# V72_A33.net
KiCad netlist of a schematic drawn in Altium Designer
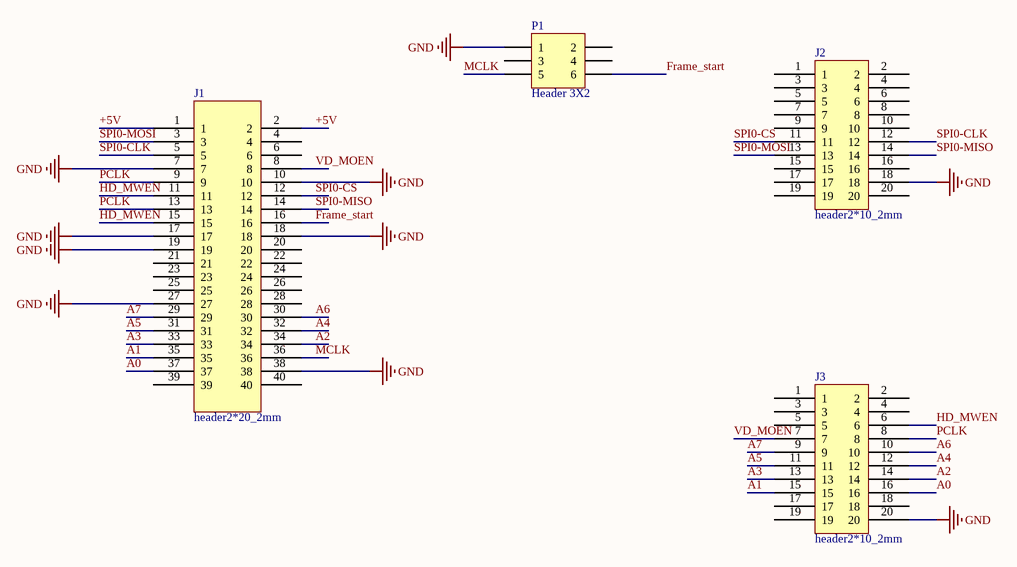
[diagram p0: V72_A33.SchDoc]

(export (version "E")
  (design (tool "Eeschema 10.0.6"))
  (components
    (comp (ref "J1")
      (value "header2*20_2mm")
      (footprint "header2*20_2mm")
      (libsource (lib "Schlib1") (part "header2*20_2mm"))
    )
    (comp (ref "J2")
      (value "header2*10_2mm")
      (footprint "header2*10_2mm")
      (libsource (lib "Schlib1") (part "header2*10_2mm"))
    )
    (comp (ref "J3")
      (value "header2*10_2mm")
      (footprint "header2*10_2mm")
      (libsource (lib "Schlib1") (part "header2*10_2mm"))
    )
    (comp (ref "P1")
      (value "Header 3X2")
      (footprint "HDR2X3")
      (description "Header, 3-Pin, Dual row")
      (fields (field (name "PUBLISHER") "Altium Limited"))
      (libsource (lib "Miscellaneous Connectors") (part "Header 3X2"))
    )
  )
  (nets
    (net (code "1") (name "/+5V") (class "Default")
      (node (ref "J1") (pin "1") (pinfunction "1_1") (pintype "passive"))
      (node (ref "J1") (pin "2") (pinfunction "2_2") (pintype "passive"))
    )
    (net (code "2") (name "/A0") (class "Default")
      (node (ref "J1") (pin "37") (pinfunction "37_37") (pintype "passive"))
      (node (ref "J3") (pin "16") (pinfunction "16_16") (pintype "passive"))
    )
    (net (code "3") (name "/A1") (class "Default")
      (node (ref "J1") (pin "35") (pinfunction "35_35") (pintype "passive"))
      (node (ref "J3") (pin "15") (pinfunction "15_15") (pintype "passive"))
    )
    (net (code "4") (name "/A2") (class "Default")
      (node (ref "J1") (pin "34") (pinfunction "34_34") (pintype "passive"))
      (node (ref "J3") (pin "14") (pinfunction "14_14") (pintype "passive"))
    )
    (net (code "5") (name "/A3") (class "Default")
      (node (ref "J1") (pin "33") (pinfunction "33_33") (pintype "passive"))
      (node (ref "J3") (pin "13") (pinfunction "13_13") (pintype "passive"))
    )
    (net (code "6") (name "/A4") (class "Default")
      (node (ref "J1") (pin "32") (pinfunction "32_32") (pintype "passive"))
      (node (ref "J3") (pin "12") (pinfunction "12_12") (pintype "passive"))
    )
    (net (code "7") (name "/A5") (class "Default")
      (node (ref "J1") (pin "31") (pinfunction "31_31") (pintype "passive"))
      (node (ref "J3") (pin "11") (pinfunction "11_11") (pintype "passive"))
    )
    (net (code "8") (name "/A6") (class "Default")
      (node (ref "J1") (pin "30") (pinfunction "30_30") (pintype "passive"))
      (node (ref "J3") (pin "10") (pinfunction "10_10") (pintype "passive"))
    )
    (net (code "9") (name "/A7") (class "Default")
      (node (ref "J1") (pin "29") (pinfunction "29_29") (pintype "passive"))
      (node (ref "J3") (pin "9") (pinfunction "9_9") (pintype "passive"))
    )
    (net (code "10") (name "/Frame_start") (class "Default")
      (node (ref "J1") (pin "16") (pinfunction "16_16") (pintype "passive"))
      (node (ref "P1") (pin "6") (pinfunction "6_6") (pintype "passive"))
    )
    (net (code "11") (name "/HD_MWEN") (class "Default")
      (node (ref "J1") (pin "11") (pinfunction "11_11") (pintype "passive"))
      (node (ref "J1") (pin "15") (pinfunction "15_15") (pintype "passive"))
      (node (ref "J3") (pin "6") (pinfunction "6_6") (pintype "passive"))
    )
    (net (code "12") (name "/MCLK") (class "Default")
      (node (ref "J1") (pin "36") (pinfunction "36_36") (pintype "passive"))
      (node (ref "P1") (pin "5") (pinfunction "5_5") (pintype "passive"))
    )
    (net (code "13") (name "/PCLK") (class "Default")
      (node (ref "J1") (pin "13") (pinfunction "13_13") (pintype "passive"))
      (node (ref "J1") (pin "9") (pinfunction "9_9") (pintype "passive"))
      (node (ref "J3") (pin "8") (pinfunction "8_8") (pintype "passive"))
    )
    (net (code "14") (name "/SPI0-CLK") (class "Default")
      (node (ref "J1") (pin "5") (pinfunction "5_5") (pintype "passive"))
      (node (ref "J2") (pin "12") (pinfunction "12_12") (pintype "passive"))
    )
    (net (code "15") (name "/SPI0-CS") (class "Default")
      (node (ref "J1") (pin "12") (pinfunction "12_12") (pintype "passive"))
      (node (ref "J2") (pin "11") (pinfunction "11_11") (pintype "passive"))
    )
    (net (code "16") (name "/SPI0-MISO") (class "Default")
      (node (ref "J1") (pin "14") (pinfunction "14_14") (pintype "passive"))
      (node (ref "J2") (pin "14") (pinfunction "14_14") (pintype "passive"))
    )
    (net (code "17") (name "/SPI0-MOSI") (class "Default")
      (node (ref "J1") (pin "3") (pinfunction "3_3") (pintype "passive"))
      (node (ref "J2") (pin "13") (pinfunction "13_13") (pintype "passive"))
    )
    (net (code "18") (name "/VD_MOEN") (class "Default")
      (node (ref "J1") (pin "8") (pinfunction "8_8") (pintype "passive"))
      (node (ref "J3") (pin "7") (pinfunction "7_7") (pintype "passive"))
    )
    (net (code "19") (name "GND") (class "Default")
      (node (ref "J1") (pin "10") (pinfunction "10_10") (pintype "passive"))
      (node (ref "J1") (pin "17") (pinfunction "17_17") (pintype "passive"))
      (node (ref "J1") (pin "18") (pinfunction "18_18") (pintype "passive"))
      (node (ref "J1") (pin "19") (pinfunction "19_19") (pintype "passive"))
      (node (ref "J1") (pin "27") (pinfunction "27_27") (pintype "passive"))
      (node (ref "J1") (pin "38") (pinfunction "38_38") (pintype "passive"))
      (node (ref "J1") (pin "7") (pinfunction "7_7") (pintype "passive"))
      (node (ref "J2") (pin "18") (pinfunction "18_18") (pintype "passive"))
      (node (ref "J3") (pin "20") (pinfunction "20_20") (pintype "passive"))
      (node (ref "P1") (pin "1") (pinfunction "1_1") (pintype "passive"))
    )
    (net (code "20") (name "unconnected-(J1-Pad4)") (class "Default")
      (node (ref "J1") (pin "4") (pinfunction "4_4") (pintype "passive"))
    )
    (net (code "21") (name "unconnected-(J1-Pad6)") (class "Default")
      (node (ref "J1") (pin "6") (pinfunction "6_6") (pintype "passive"))
    )
    (net (code "22") (name "unconnected-(J1-Pad20)") (class "Default")
      (node (ref "J1") (pin "20") (pinfunction "20_20") (pintype "passive"))
    )
    (net (code "23") (name "unconnected-(J1-Pad21)") (class "Default")
      (node (ref "J1") (pin "21") (pinfunction "21_21") (pintype "passive"))
    )
    (net (code "24") (name "unconnected-(J1-Pad22)") (class "Default")
      (node (ref "J1") (pin "22") (pinfunction "22_22") (pintype "passive"))
    )
    (net (code "25") (name "unconnected-(J1-Pad23)") (class "Default")
      (node (ref "J1") (pin "23") (pinfunction "23_23") (pintype "passive"))
    )
    (net (code "26") (name "unconnected-(J1-Pad24)") (class "Default")
      (node (ref "J1") (pin "24") (pinfunction "24_24") (pintype "passive"))
    )
    (net (code "27") (name "unconnected-(J1-Pad25)") (class "Default")
      (node (ref "J1") (pin "25") (pinfunction "25_25") (pintype "passive"))
    )
    (net (code "28") (name "unconnected-(J1-Pad26)") (class "Default")
      (node (ref "J1") (pin "26") (pinfunction "26_26") (pintype "passive"))
    )
    (net (code "29") (name "unconnected-(J1-Pad28)") (class "Default")
      (node (ref "J1") (pin "28") (pinfunction "28_28") (pintype "passive"))
    )
    (net (code "30") (name "unconnected-(J1-Pad39)") (class "Default")
      (node (ref "J1") (pin "39") (pinfunction "39_39") (pintype "passive"))
    )
    (net (code "31") (name "unconnected-(J1-Pad40)") (class "Default")
      (node (ref "J1") (pin "40") (pinfunction "40_40") (pintype "passive"))
    )
    (net (code "32") (name "unconnected-(J2-Pad1)") (class "Default")
      (node (ref "J2") (pin "1") (pinfunction "1_1") (pintype "passive"))
    )
    (net (code "33") (name "unconnected-(J2-Pad2)") (class "Default")
      (node (ref "J2") (pin "2") (pinfunction "2_2") (pintype "passive"))
    )
    (net (code "34") (name "unconnected-(J2-Pad3)") (class "Default")
      (node (ref "J2") (pin "3") (pinfunction "3_3") (pintype "passive"))
    )
    (net (code "35") (name "unconnected-(J2-Pad4)") (class "Default")
      (node (ref "J2") (pin "4") (pinfunction "4_4") (pintype "passive"))
    )
    (net (code "36") (name "unconnected-(J2-Pad5)") (class "Default")
      (node (ref "J2") (pin "5") (pinfunction "5_5") (pintype "passive"))
    )
    (net (code "37") (name "unconnected-(J2-Pad6)") (class "Default")
      (node (ref "J2") (pin "6") (pinfunction "6_6") (pintype "passive"))
    )
    (net (code "38") (name "unconnected-(J2-Pad7)") (class "Default")
      (node (ref "J2") (pin "7") (pinfunction "7_7") (pintype "passive"))
    )
    (net (code "39") (name "unconnected-(J2-Pad8)") (class "Default")
      (node (ref "J2") (pin "8") (pinfunction "8_8") (pintype "passive"))
    )
    (net (code "40") (name "unconnected-(J2-Pad9)") (class "Default")
      (node (ref "J2") (pin "9") (pinfunction "9_9") (pintype "passive"))
    )
    (net (code "41") (name "unconnected-(J2-Pad10)") (class "Default")
      (node (ref "J2") (pin "10") (pinfunction "10_10") (pintype "passive"))
    )
    (net (code "42") (name "unconnected-(J2-Pad15)") (class "Default")
      (node (ref "J2") (pin "15") (pinfunction "15_15") (pintype "passive"))
    )
    (net (code "43") (name "unconnected-(J2-Pad16)") (class "Default")
      (node (ref "J2") (pin "16") (pinfunction "16_16") (pintype "passive"))
    )
    (net (code "44") (name "unconnected-(J2-Pad17)") (class "Default")
      (node (ref "J2") (pin "17") (pinfunction "17_17") (pintype "passive"))
    )
    (net (code "45") (name "unconnected-(J2-Pad19)") (class "Default")
      (node (ref "J2") (pin "19") (pinfunction "19_19") (pintype "passive"))
    )
    (net (code "46") (name "unconnected-(J2-Pad20)") (class "Default")
      (node (ref "J2") (pin "20") (pinfunction "20_20") (pintype "passive"))
    )
    (net (code "47") (name "unconnected-(J3-Pad1)") (class "Default")
      (node (ref "J3") (pin "1") (pinfunction "1_1") (pintype "passive"))
    )
    (net (code "48") (name "unconnected-(J3-Pad2)") (class "Default")
      (node (ref "J3") (pin "2") (pinfunction "2_2") (pintype "passive"))
    )
    (net (code "49") (name "unconnected-(J3-Pad3)") (class "Default")
      (node (ref "J3") (pin "3") (pinfunction "3_3") (pintype "passive"))
    )
    (net (code "50") (name "unconnected-(J3-Pad4)") (class "Default")
      (node (ref "J3") (pin "4") (pinfunction "4_4") (pintype "passive"))
    )
    (net (code "51") (name "unconnected-(J3-Pad5)") (class "Default")
      (node (ref "J3") (pin "5") (pinfunction "5_5") (pintype "passive"))
    )
    (net (code "52") (name "unconnected-(J3-Pad17)") (class "Default")
      (node (ref "J3") (pin "17") (pinfunction "17_17") (pintype "passive"))
    )
    (net (code "53") (name "unconnected-(J3-Pad18)") (class "Default")
      (node (ref "J3") (pin "18") (pinfunction "18_18") (pintype "passive"))
    )
    (net (code "54") (name "unconnected-(J3-Pad19)") (class "Default")
      (node (ref "J3") (pin "19") (pinfunction "19_19") (pintype "passive"))
    )
    (net (code "55") (name "unconnected-(P1-Pad2)") (class "Default")
      (node (ref "P1") (pin "2") (pinfunction "2_2") (pintype "passive"))
    )
    (net (code "56") (name "unconnected-(P1-Pad3)") (class "Default")
      (node (ref "P1") (pin "3") (pinfunction "3_3") (pintype "passive"))
    )
    (net (code "57") (name "unconnected-(P1-Pad4)") (class "Default")
      (node (ref "P1") (pin "4") (pinfunction "4_4") (pintype "passive"))
    )
  )
)
